# ethernet_zasilanie.net
KiCad netlist of a schematic drawn in Altium Designer
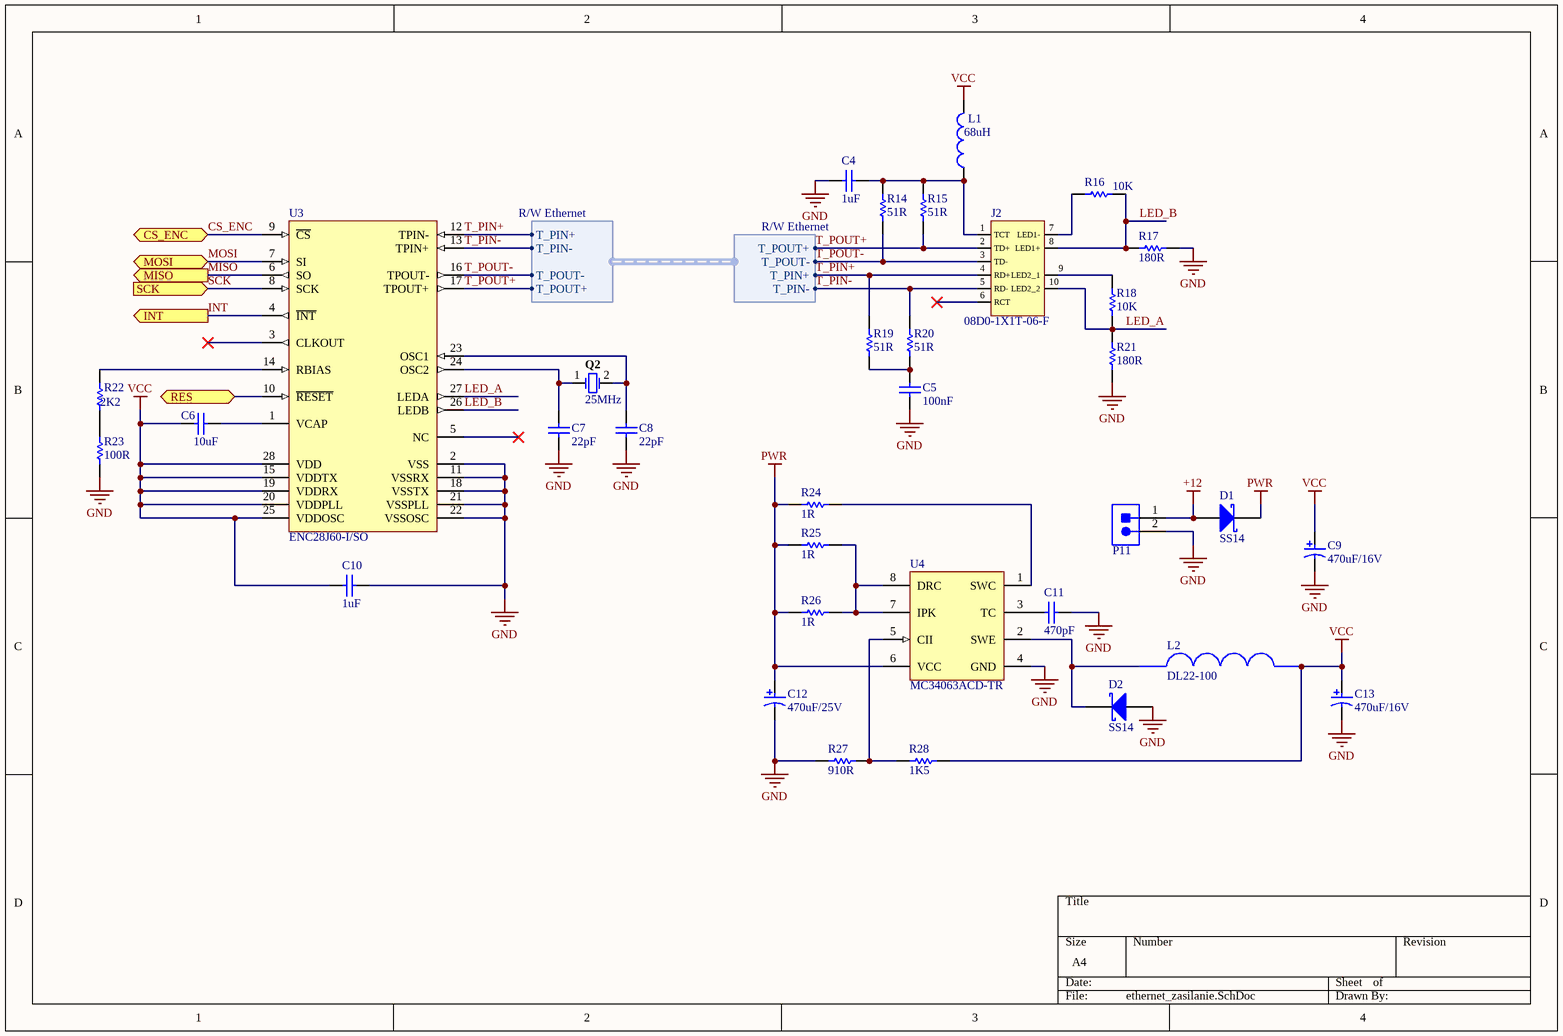
[diagram p0: ethernet_zasilanie.SchDoc]

(export (version "E")
  (design (tool "Eeschema 10.0.6"))
  (components
    (comp (ref "C4")
      (value "1uF")
      (footprint "CAPC1206(3216)150_L")
      (description "CAP 1uF 6.3V ±5% 1206 (3216 Metric) Thickness 1.45mm SMD")
      (fields (field (name "TOLERANCE") "Â±5%"))
      (libsource (lib "Altium Content Vault") (part "CAP"))
    )
    (comp (ref "C5")
      (value "100nF")
      (footprint "CAPC1206(3216)190_L")
      (description "CAP 100nF 10V ±1% 1206 (3216 Metric) Thickness 1.9mm SMD")
      (fields (field (name "TOLERANCE") "Â±1%"))
      (libsource (lib "Altium Content Vault") (part "CAP"))
    )
    (comp (ref "C6")
      (value "10uF")
      (footprint "CAPC1206(3216)190_L")
      (description "CAP 10uF 6.3V ±5% 1206 (3216 Metric) Thickness 1.9mm SMD")
      (fields (field (name "TOLERANCE") "Â±5%"))
      (libsource (lib "Altium Content Vault") (part "CAP"))
    )
    (comp (ref "C7")
      (value "22pF")
      (footprint "CAPC1206(3216)100_L")
      (description "CAP 22pF 10V ±0.25pF 1206 (3216 Metric) Thickness 1mm SMD")
      (fields (field (name "TOLERANCE") "Â±0.25pF"))
      (libsource (lib "Altium Content Vault") (part "CAP"))
    )
    (comp (ref "C8")
      (value "22pF")
      (footprint "CAPC1206(3216)100_L")
      (description "CAP 22pF 10V ±0.25pF 1206 (3216 Metric) Thickness 1mm SMD")
      (fields (field (name "TOLERANCE") "Â±0.25pF"))
      (libsource (lib "Altium Content Vault") (part "CAP"))
    )
    (comp (ref "C9")
      (value "470uF/16V")
      (footprint "PNSC-FK-V-F_V")
      (fields (field (name "MANUFACTURER") "Panasonic"))
      (libsource (lib "Altium Content Vault") (part "CAP-P-2"))
    )
    (comp (ref "C10")
      (value "1uF")
      (footprint "CAPC1206(3216)130_L")
      (description "CAP 1uF 10V ±5% 1206 (3216 Metric) Thickness 1.3mm SMD")
      (fields (field (name "TOLERANCE") "Â±5%"))
      (libsource (lib "Altium Content Vault") (part "CAP"))
    )
    (comp (ref "C11")
      (value "470pF")
      (footprint "CAPC1206(3216)100_L")
      (description "CAP 470pF 10V ±1% 1206 (3216 Metric) Thickness 1mm SMD")
      (fields (field (name "TOLERANCE") "Â±1%"))
      (libsource (lib "Altium Content Vault") (part "CAP"))
    )
    (comp (ref "C12")
      (value "470uF/25V")
      (footprint "NIC-CAPA2-10X10_V")
      (fields (field (name "PARTNUMBER") "UUD1E471MNL1GS") (field (name "MANUFACTURER") "Nichicon"))
      (libsource (lib "Altium Content Vault") (part "NIC-CAP-P-2"))
    )
    (comp (ref "C13")
      (value "470uF/16V")
      (footprint "PNSC-FK-V-F_V")
      (fields (field (name "MANUFACTURER") "Panasonic"))
      (libsource (lib "Altium Content Vault") (part "CAP-P-2"))
    )
    (comp (ref "D1")
      (value "SS14")
      (footprint "FAIR-DO-214AC-2_V")
      (description "Schottky Rectifier, 1.1 W, -65 to 125 degC, 2-Pin SMD, RoHS, Tape and Reel")
      (fields (field (name "MANUFACTURER") "Fairchild"))
      (libsource (lib "Altium Content Vault") (part "DSKY-KA-2"))
    )
    (comp (ref "D2")
      (value "SS14")
      (footprint "FAIR-DO-214AC-2_V")
      (description "Schottky Rectifier, 1.1 W, -65 to 125 degC, 2-Pin SMD, RoHS, Tape and Reel")
      (fields (field (name "MANUFACTURER") "Fairchild"))
      (libsource (lib "Altium Content Vault") (part "DSKY-KA-2"))
    )
    (comp (ref "J2")
      (value "08D0-1X1T-06-F")
      (footprint "PCB_08D0-1X1T-06-F")
      (libsource (lib "PKSchlib") (part "08D0-1X1T-06-F"))
    )
    (comp (ref "L1")
      (value "68uH")
      (footprint "INDC1608L")
      (description "Inductor")
      (fields (field (name "PUBLISHER") "Altium Limited"))
      (libsource (lib "Miscellaneous Devices") (part "Inductor"))
    )
    (comp (ref "L2") (value "DL22-100") (footprint "DL22") (libsource (lib "Dodatkowe") (part "DL22-100")))
    (comp (ref "P11")
      (value "SCREW-5.0/5.08 2WAYS")
      (footprint "SCREW-5.0-2WAYS_V")
      (description "Socket, Screw Terminal Block, 2 Way, 5.0 mm Pitch, 90 Degree Angle, Through-Hole")
      (fields (field (name "MANUFACTURER") "No Vendor"))
      (libsource (lib "Altium Content Vault") (part "SCREW-2WAYS"))
    )
    (comp (ref "Q2")
      (value "25MHz")
      (footprint "JPY-HC-49US")
      (description "Crystal, 25 MHz, +/- 30 ppm, 22 pF, -20 to 70 degC, 2-Pin THD")
      (fields (field (name "MANUFACTURER") "Jing peng yuan"))
      (libsource (lib "Altium Content Vault") (part "XTAL-1-2-2"))
    )
    (comp (ref "R14")
      (value "51R")
      (footprint "RESC1206(3216)_L")
      (description "51R 0.25W 1% 1206 (3216 Metric)  SMD")
      (fields (field (name "TOLERANCE") "1 %") (field (name "POWER") "0.25 W"))
      (libsource (lib "Altium Content Vault") (part "RES"))
    )
    (comp (ref "R15")
      (value "51R")
      (footprint "RESC1206(3216)_L")
      (description "51R 0.25W 1% 1206 (3216 Metric)  SMD")
      (fields (field (name "TOLERANCE") "1 %") (field (name "POWER") "0.25 W"))
      (libsource (lib "Altium Content Vault") (part "RES"))
    )
    (comp (ref "R16")
      (value "10K")
      (footprint "RESC1206(3216)_L")
      (description "10K 0.25W 1% 1206 (3216 Metric)  SMD")
      (fields (field (name "POWER") "0.25 W") (field (name "TOLERANCE") "1 %"))
      (libsource (lib "Altium Content Vault") (part "RES"))
    )
    (comp (ref "R17")
      (value "180R")
      (footprint "RESC1206(3216)_L")
      (description "180R 0.25W 1% 1206 (3216 Metric)  SMD")
      (fields (field (name "TOLERANCE") "1 %") (field (name "POWER") "0.25 W"))
      (libsource (lib "Altium Content Vault") (part "RES"))
    )
    (comp (ref "R18")
      (value "10K")
      (footprint "RESC1206(3216)_L")
      (description "10K 0.25W 1% 1206 (3216 Metric)  SMD")
      (fields (field (name "POWER") "0.25 W") (field (name "TOLERANCE") "1 %"))
      (libsource (lib "Altium Content Vault") (part "RES"))
    )
    (comp (ref "R19")
      (value "51R")
      (footprint "RESC1206(3216)_L")
      (description "51R 0.25W 1% 1206 (3216 Metric)  SMD")
      (fields (field (name "TOLERANCE") "1 %") (field (name "POWER") "0.25 W"))
      (libsource (lib "Altium Content Vault") (part "RES"))
    )
    (comp (ref "R20")
      (value "51R")
      (footprint "RESC1206(3216)_L")
      (description "51R 0.25W 1% 1206 (3216 Metric)  SMD")
      (fields (field (name "TOLERANCE") "1 %") (field (name "POWER") "0.25 W"))
      (libsource (lib "Altium Content Vault") (part "RES"))
    )
    (comp (ref "R21")
      (value "180R")
      (footprint "RESC1206(3216)_L")
      (description "180R 0.25W 1% 1206 (3216 Metric)  SMD")
      (fields (field (name "TOLERANCE") "1 %") (field (name "POWER") "0.25 W"))
      (libsource (lib "Altium Content Vault") (part "RES"))
    )
    (comp (ref "R22")
      (value "2K2")
      (footprint "RESC1206(3216)_L")
      (description "2K2 0.25W 1% 1206 (3216 Metric)  SMD")
      (fields (field (name "POWER") "0.25 W") (field (name "TOLERANCE") "1 %"))
      (libsource (lib "Altium Content Vault") (part "RES"))
    )
    (comp (ref "R23")
      (value "100R")
      (footprint "RESC1206(3216)_L")
      (description "100R 0.25W 1% 1206 (3216 Metric)  SMD")
      (fields (field (name "TOLERANCE") "1 %") (field (name "POWER") "0.25 W"))
      (libsource (lib "Altium Content Vault") (part "RES"))
    )
    (comp (ref "R24")
      (value "1R")
      (footprint "RESC1206(3216)_L")
      (description "1R 0.25W 1% 1206 (3216 Metric)  SMD")
      (fields (field (name "POWER") "0.25 W") (field (name "TOLERANCE") "1 %"))
      (libsource (lib "Altium Content Vault") (part "RES"))
    )
    (comp (ref "R25")
      (value "1R")
      (footprint "RESC1206(3216)_L")
      (description "1R 0.25W 1% 1206 (3216 Metric)  SMD")
      (fields (field (name "POWER") "0.25 W") (field (name "TOLERANCE") "1 %"))
      (libsource (lib "Altium Content Vault") (part "RES"))
    )
    (comp (ref "R26")
      (value "1R")
      (footprint "RESC1206(3216)_L")
      (description "1R 0.25W 1% 1206 (3216 Metric)  SMD")
      (fields (field (name "POWER") "0.25 W") (field (name "TOLERANCE") "1 %"))
      (libsource (lib "Altium Content Vault") (part "RES"))
    )
    (comp (ref "R27")
      (value "910R")
      (footprint "RESC1206(3216)_L")
      (description "910R 0.25W 1% 1206 (3216 Metric)  SMD")
      (fields (field (name "POWER") "0.25 W") (field (name "TOLERANCE") "1 %"))
      (libsource (lib "Altium Content Vault") (part "RES"))
    )
    (comp (ref "R28")
      (value "1K5")
      (footprint "RESC1206(3216)_L")
      (description "1K5 0.25W 1% 1206 (3216 Metric)  SMD")
      (fields (field (name "TOLERANCE") "1 %") (field (name "POWER") "0.25 W"))
      (libsource (lib "Altium Content Vault") (part "RES"))
    )
    (comp (ref "U3")
      (value "ENC28J60-I/SO")
      (footprint "SOIC-SO28_L")
      (description "Stand-Alone Ethernet Controller with SPI Interface, 28-Pin SOIC, Industrial Temperature")
      (libsource (lib "Altium Content Vault") (part "COM-ENET-ENC28J60-28"))
    )
    (comp (ref "U4")
      (value "MC34063ACD-TR")
      (footprint "SO8_L")
      (description "DC/DC converter control circuit, 8-Pin SO, Tape and Reel")
      (libsource (lib "Altium Content Vault") (part "PM-SWREG-MC34063-IL8"))
    )
  )
  (nets
    (net (code "3") (name "+12") (class "Default")
      (node (ref "D1") (pin "2") (pinfunction "A_2") (pintype "passive"))
      (node (ref "P11") (pin "1") (pinfunction "1_1") (pintype "passive"))
    )
    (net (code "4") (name "/CS_ENC") (class "Default")
      (node (ref "U3") (pin "9") (pinfunction "~{CS}_9") (pintype "input"))
    )
    (net (code "5") (name "/INT") (class "Default")
      (node (ref "U3") (pin "4") (pinfunction "~{INT}_4") (pintype "output"))
    )
    (net (code "6") (name "/LED_A") (class "Default")
      (node (ref "J2") (pin "10") (pinfunction "LED2_2_10") (pintype "passive"))
      (node (ref "R18") (pin "1") (pinfunction "1_1") (pintype "passive"))
      (node (ref "R21") (pin "2") (pinfunction "2_2") (pintype "passive"))
      (node (ref "U3") (pin "27") (pinfunction "LEDA_27") (pintype "output"))
    )
    (net (code "7") (name "/LED_B") (class "Default")
      (node (ref "J2") (pin "8") (pinfunction "LED1+_8") (pintype "passive"))
      (node (ref "R16") (pin "1") (pinfunction "1_1") (pintype "passive"))
      (node (ref "R17") (pin "1") (pinfunction "1_1") (pintype "passive"))
      (node (ref "U3") (pin "26") (pinfunction "LEDB_26") (pintype "output"))
    )
    (net (code "8") (name "/MISO") (class "Default")
      (node (ref "U3") (pin "6") (pinfunction "SO_6") (pintype "output"))
    )
    (net (code "9") (name "/MOSI") (class "Default")
      (node (ref "U3") (pin "7") (pinfunction "SI_7") (pintype "input"))
    )
    (net (code "10") (name "/RES") (class "Default")
      (node (ref "U3") (pin "10") (pinfunction "~{RESET}_10") (pintype "input"))
    )
    (net (code "11") (name "/SCK") (class "Default")
      (node (ref "U3") (pin "8") (pinfunction "SCK_8") (pintype "input"))
    )
    (net (code "12") (name "/T_PIN+") (class "Default")
      (node (ref "J2") (pin "4") (pinfunction "RD+_4") (pintype "passive"))
      (node (ref "R19") (pin "2") (pinfunction "2_2") (pintype "passive"))
      (node (ref "U3") (pin "12") (pinfunction "TPIN-_12") (pintype "input"))
    )
    (net (code "13") (name "/T_PIN-") (class "Default")
      (node (ref "J2") (pin "5") (pinfunction "RD-_5") (pintype "passive"))
      (node (ref "R20") (pin "2") (pinfunction "2_2") (pintype "passive"))
      (node (ref "U3") (pin "13") (pinfunction "TPIN+_13") (pintype "input"))
    )
    (net (code "14") (name "/T_POUT+") (class "Default")
      (node (ref "J2") (pin "2") (pinfunction "TD+_2") (pintype "passive"))
      (node (ref "R15") (pin "1") (pinfunction "1_1") (pintype "passive"))
      (node (ref "U3") (pin "17") (pinfunction "TPOUT+_17") (pintype "output"))
    )
    (net (code "15") (name "/T_POUT-") (class "Default")
      (node (ref "J2") (pin "3") (pinfunction "TD-_3") (pintype "passive"))
      (node (ref "R14") (pin "1") (pinfunction "1_1") (pintype "passive"))
      (node (ref "U3") (pin "16") (pinfunction "TPOUT-_16") (pintype "output"))
    )
    (net (code "17") (name "GND") (class "Default")
      (node (ref "C10") (pin "1") (pinfunction "1_1") (pintype "passive"))
      (node (ref "C11") (pin "2") (pinfunction "2_2") (pintype "passive"))
      (node (ref "C12") (pin "2") (pinfunction "2_2") (pintype "passive"))
      (node (ref "C13") (pin "2") (pinfunction "2_2") (pintype "passive"))
      (node (ref "C4") (pin "1") (pinfunction "1_1") (pintype "passive"))
      (node (ref "C5") (pin "1") (pinfunction "1_1") (pintype "passive"))
      (node (ref "C7") (pin "1") (pinfunction "1_1") (pintype "passive"))
      (node (ref "C8") (pin "1") (pinfunction "1_1") (pintype "passive"))
      (node (ref "C9") (pin "2") (pinfunction "2_2") (pintype "passive"))
      (node (ref "D2") (pin "2") (pinfunction "A_2") (pintype "passive"))
      (node (ref "P11") (pin "2") (pinfunction "2_2") (pintype "passive"))
      (node (ref "R17") (pin "2") (pinfunction "2_2") (pintype "passive"))
      (node (ref "R21") (pin "1") (pinfunction "1_1") (pintype "passive"))
      (node (ref "R23") (pin "1") (pinfunction "1_1") (pintype "passive"))
      (node (ref "R27") (pin "1") (pinfunction "1_1") (pintype "passive"))
      (node (ref "U3") (pin "11") (pinfunction "VSSRX_11") (pintype "power_in"))
      (node (ref "U3") (pin "18") (pinfunction "VSSTX_18") (pintype "power_in"))
      (node (ref "U3") (pin "2") (pinfunction "VSS_2") (pintype "power_in"))
      (node (ref "U3") (pin "21") (pinfunction "VSSPLL_21") (pintype "power_in"))
      (node (ref "U3") (pin "22") (pinfunction "VSSOSC_22") (pintype "power_in"))
      (node (ref "U4") (pin "4") (pinfunction "GND_4") (pintype "power_in"))
    )
    (net (code "18") (name "Net-(C5-Pad2)") (class "Default")
      (node (ref "C5") (pin "2") (pinfunction "2_2") (pintype "passive"))
      (node (ref "R19") (pin "1") (pinfunction "1_1") (pintype "passive"))
      (node (ref "R20") (pin "1") (pinfunction "1_1") (pintype "passive"))
    )
    (net (code "19") (name "Net-(D2-K)") (class "Default")
      (node (ref "D2") (pin "1") (pinfunction "K_1") (pintype "passive"))
      (node (ref "L2") (pin "1") (pinfunction "1_1") (pintype "passive"))
      (node (ref "U4") (pin "2") (pinfunction "SWE_2") (pintype "open_emitter"))
    )
    (net (code "20") (name "Net-(J2-LED1-)") (class "Default")
      (node (ref "J2") (pin "7") (pinfunction "LED1-_7") (pintype "passive"))
      (node (ref "R16") (pin "2") (pinfunction "2_2") (pintype "passive"))
    )
    (net (code "21") (name "Net-(J2-LED2_1)") (class "Default")
      (node (ref "J2") (pin "9") (pinfunction "LED2_1_9") (pintype "passive"))
      (node (ref "R18") (pin "2") (pinfunction "2_2") (pintype "passive"))
    )
    (net (code "22") (name "Net-(J2-TCT)") (class "Default")
      (node (ref "C4") (pin "2") (pinfunction "2_2") (pintype "passive"))
      (node (ref "J2") (pin "1") (pinfunction "TCT_1") (pintype "passive"))
      (node (ref "L1") (pin "1") (pinfunction "1_1") (pintype "passive"))
      (node (ref "R14") (pin "2") (pinfunction "2_2") (pintype "passive"))
      (node (ref "R15") (pin "2") (pinfunction "2_2") (pintype "passive"))
    )
    (net (code "23") (name "Net-(R22-Pad1)") (class "Default")
      (node (ref "R22") (pin "1") (pinfunction "1_1") (pintype "passive"))
      (node (ref "R23") (pin "2") (pinfunction "2_2") (pintype "passive"))
    )
    (net (code "24") (name "Net-(U3-OSC1)") (class "Default")
      (node (ref "C8") (pin "2") (pinfunction "2_2") (pintype "passive"))
      (node (ref "Q2") (pin "2") (pinfunction "2_2") (pintype "passive"))
      (node (ref "U3") (pin "23") (pinfunction "OSC1_23") (pintype "input"))
    )
    (net (code "25") (name "Net-(U3-OSC2)") (class "Default")
      (node (ref "C7") (pin "2") (pinfunction "2_2") (pintype "passive"))
      (node (ref "Q2") (pin "1") (pinfunction "1_1") (pintype "passive"))
      (node (ref "U3") (pin "24") (pinfunction "OSC2_24") (pintype "output"))
    )
    (net (code "26") (name "Net-(U3-RBIAS)") (class "Default")
      (node (ref "R22") (pin "2") (pinfunction "2_2") (pintype "passive"))
      (node (ref "U3") (pin "14") (pinfunction "RBIAS_14") (pintype "input"))
    )
    (net (code "27") (name "Net-(U3-VCAP)") (class "Default")
      (node (ref "C6") (pin "2") (pinfunction "2_2") (pintype "passive"))
      (node (ref "U3") (pin "1") (pinfunction "VCAP_1") (pintype "power_in"))
    )
    (net (code "28") (name "Net-(U4-CII)") (class "Default")
      (node (ref "R27") (pin "2") (pinfunction "2_2") (pintype "passive"))
      (node (ref "R28") (pin "1") (pinfunction "1_1") (pintype "passive"))
      (node (ref "U4") (pin "5") (pinfunction "CII_5") (pintype "input"))
    )
    (net (code "29") (name "Net-(U4-DRC)") (class "Default")
      (node (ref "R25") (pin "2") (pinfunction "2_2") (pintype "passive"))
      (node (ref "R26") (pin "2") (pinfunction "2_2") (pintype "passive"))
      (node (ref "U4") (pin "7") (pinfunction "IPK_7") (pintype "passive"))
      (node (ref "U4") (pin "8") (pinfunction "DRC_8") (pintype "open_collector"))
    )
    (net (code "30") (name "Net-(U4-SWC)") (class "Default")
      (node (ref "R24") (pin "2") (pinfunction "2_2") (pintype "passive"))
      (node (ref "U4") (pin "1") (pinfunction "SWC_1") (pintype "open_collector"))
    )
    (net (code "31") (name "Net-(U4-TC)") (class "Default")
      (node (ref "C11") (pin "1") (pinfunction "1_1") (pintype "passive"))
      (node (ref "U4") (pin "3") (pinfunction "TC_3") (pintype "passive"))
    )
    (net (code "32") (name "PWR") (class "Default")
      (node (ref "C12") (pin "1") (pinfunction "1_1") (pintype "passive"))
      (node (ref "D1") (pin "1") (pinfunction "K_1") (pintype "passive"))
      (node (ref "R24") (pin "1") (pinfunction "1_1") (pintype "passive"))
      (node (ref "R25") (pin "1") (pinfunction "1_1") (pintype "passive"))
      (node (ref "R26") (pin "1") (pinfunction "1_1") (pintype "passive"))
      (node (ref "U4") (pin "6") (pinfunction "VCC_6") (pintype "power_in"))
    )
    (net (code "33") (name "VCC") (class "Default")
      (node (ref "C10") (pin "2") (pinfunction "2_2") (pintype "passive"))
      (node (ref "C13") (pin "1") (pinfunction "1_1") (pintype "passive"))
      (node (ref "C6") (pin "1") (pinfunction "1_1") (pintype "passive"))
      (node (ref "C9") (pin "1") (pinfunction "1_1") (pintype "passive"))
      (node (ref "L1") (pin "2") (pinfunction "2_2") (pintype "passive"))
      (node (ref "L2") (pin "2") (pinfunction "2_2") (pintype "passive"))
      (node (ref "R28") (pin "2") (pinfunction "2_2") (pintype "passive"))
      (node (ref "U3") (pin "15") (pinfunction "VDDTX_15") (pintype "power_in"))
      (node (ref "U3") (pin "19") (pinfunction "VDDRX_19") (pintype "power_in"))
      (node (ref "U3") (pin "20") (pinfunction "VDDPLL_20") (pintype "power_in"))
      (node (ref "U3") (pin "25") (pinfunction "VDDOSC_25") (pintype "power_in"))
      (node (ref "U3") (pin "28") (pinfunction "VDD_28") (pintype "power_in"))
    )
    (net (code "34") (name "unconnected-(J2-RCT-Pad6)") (class "Default")
      (node (ref "J2") (pin "6") (pinfunction "RCT_6") (pintype "passive+no_connect"))
    )
    (net (code "35") (name "unconnected-(U3-CLKOUT-Pad3)") (class "Default")
      (node (ref "U3") (pin "3") (pinfunction "CLKOUT_3") (pintype "output+no_connect"))
    )
    (net (code "36") (name "unconnected-(U3-NC-Pad5)") (class "Default")
      (node (ref "U3") (pin "5") (pinfunction "NC_5") (pintype "passive+no_connect"))
    )
  )
)
